# general_Interface.net
KiCad netlist of a schematic drawn in Altium Designer
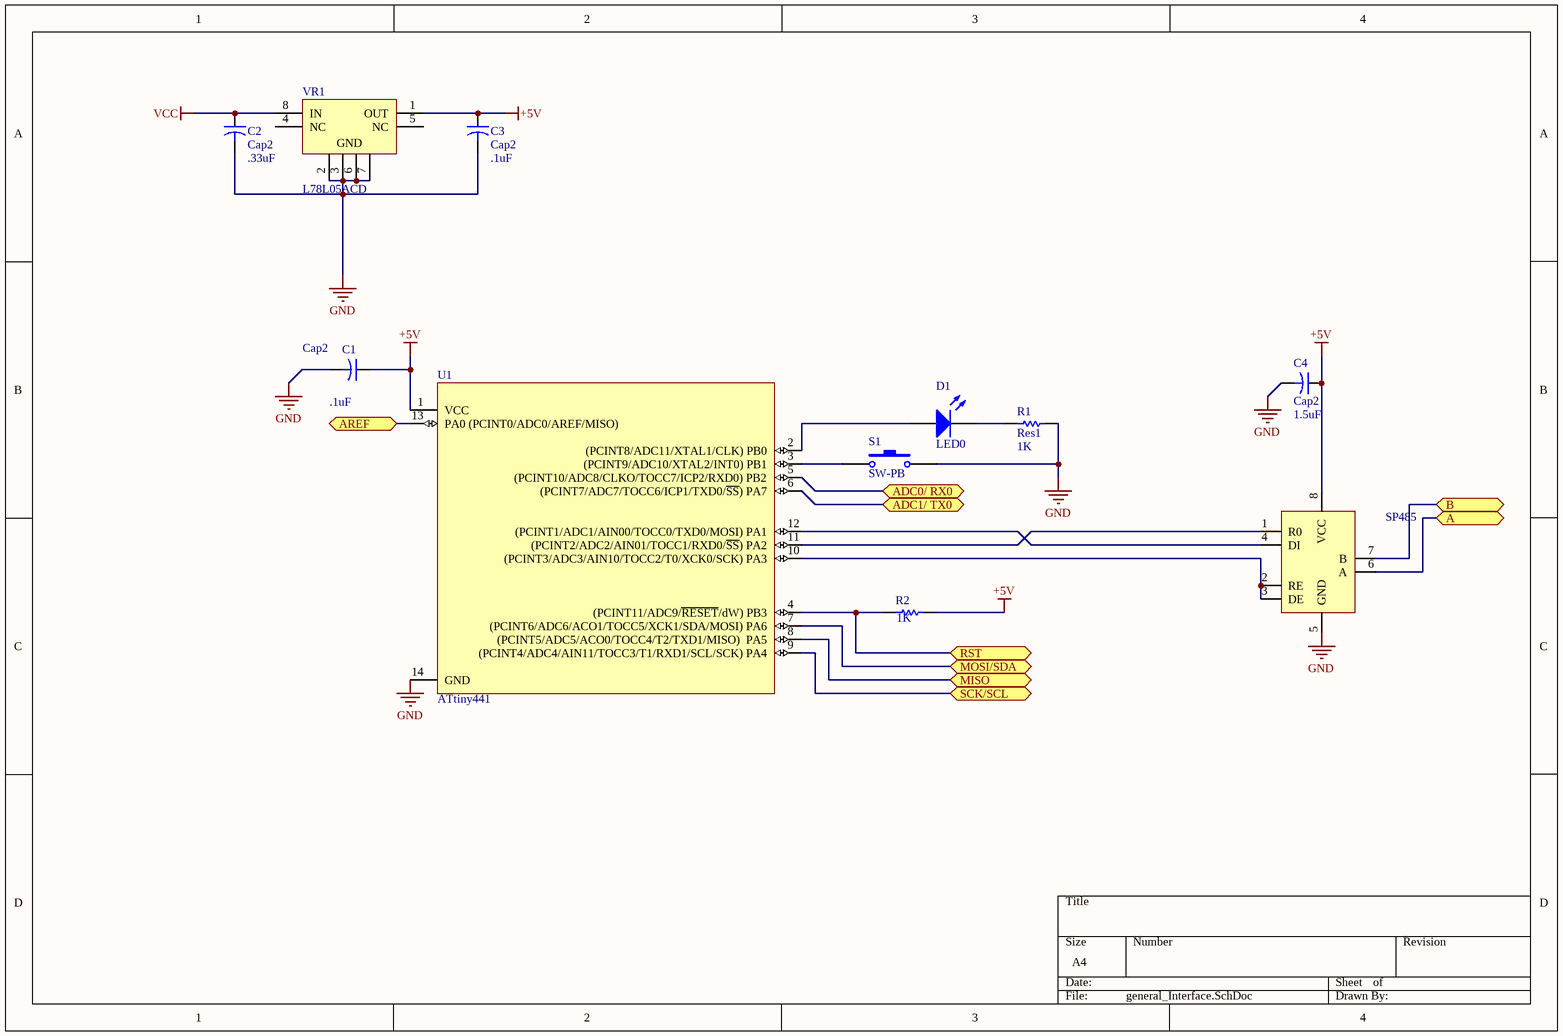
[diagram p0: general_Interface.SchDoc]

(export (version "E")
  (design (tool "Eeschema 10.0.6"))
  (components
    (comp (ref "C1")
      (value "Cap2")
      (footprint "6-0805_N")
      (description "Capacitor")
      (fields (field (name "ALTIUM_VALUE") ".1uF") (field (name "PUBLISHER") "Altium Limited"))
      (libsource (lib "Miscellaneous Devices") (part "Cap2"))
    )
    (comp (ref "C2")
      (value "Cap2")
      (footprint "6-0805_N")
      (description "Capacitor")
      (fields (field (name "ALTIUM_VALUE") ".33uF") (field (name "PUBLISHER") "Altium Limited"))
      (libsource (lib "Miscellaneous Devices") (part "Cap2"))
    )
    (comp (ref "C3")
      (value "Cap2")
      (footprint "6-0805_N")
      (description "Capacitor")
      (fields (field (name "ALTIUM_VALUE") ".1uF") (field (name "PUBLISHER") "Altium Limited"))
      (libsource (lib "Miscellaneous Devices") (part "Cap2"))
    )
    (comp (ref "C4")
      (value "Cap2")
      (footprint "6-0805_N")
      (description "Capacitor")
      (fields (field (name "ALTIUM_VALUE") "1.5uF") (field (name "PUBLISHER") "Altium Limited"))
      (libsource (lib "Miscellaneous Devices") (part "Cap2"))
    )
    (comp (ref "D1")
      (value "LED0")
      (footprint "1608[0603]")
      (description "Typical INFRARED GaAs LED")
      (fields (field (name "PUBLISHER") "Altium Limited"))
      (libsource (lib "Miscellaneous Devices") (part "LED0"))
    )
    (comp (ref "R1")
      (value "Res1")
      (footprint "6-0805_N")
      (description "Resistor")
      (fields (field (name "ALTIUM_VALUE") "1K") (field (name "PUBLISHER") "Altium Limited"))
      (libsource (lib "Miscellaneous Devices") (part "Res1"))
    )
    (comp (ref "R2")
      (value "1K")
      (footprint "6-0805_N")
      (description "Resistor")
      (fields (field (name "Comment") "Res1") (field (name "PUBLISHER") "Altium Limited"))
      (libsource (lib "Miscellaneous Devices") (part "Res1"))
    )
    (comp (ref "S1")
      (value "SW-PB")
      (footprint "ADTSM3")
      (description "Switch")
      (fields (field (name "PUBLISHER") "Altium Limited"))
      (libsource (lib "Miscellaneous Devices") (part "SW-PB"))
    )
    (comp (ref "SP485") (value "SP485") (footprint "8S1_M") (libsource (lib "MABSS") (part "SP485")))
    (comp (ref "U1") (value "ATtiny441") (footprint "6ST1_L") (libsource (lib "MABSS") (part "ATtiny441")))
    (comp (ref "VR1")
      (value "L78L05ACD")
      (footprint "SO8_N")
      (description "Positive Voltage Regulator")
      (fields (field (name "PUBLISHER") "Altium Limited"))
      (libsource (lib "ST Power Mgt Voltage Regulator") (part "L78L05ACD"))
    )
  )
  (nets
    (net (code "1") (name "+5V") (class "Default")
      (node (ref "C1") (pin "1") (pinfunction "1_1") (pintype "passive"))
      (node (ref "C3") (pin "1") (pinfunction "1_1") (pintype "passive"))
      (node (ref "C4") (pin "1") (pinfunction "1_1") (pintype "passive"))
      (node (ref "R2") (pin "2") (pinfunction "2_2") (pintype "passive"))
      (node (ref "SP485") (pin "8") (pinfunction "VCC_8") (pintype "passive"))
      (node (ref "U1") (pin "1") (pinfunction "VCC_1") (pintype "power_in"))
      (node (ref "VR1") (pin "1") (pinfunction "OUT_1") (pintype "power_in"))
    )
    (net (code "2") (name "/A") (class "Default")
      (node (ref "SP485") (pin "6") (pinfunction "A_6") (pintype "passive"))
    )
    (net (code "3") (name "/ADC0{slash} RX0") (class "Default")
      (node (ref "U1") (pin "5") (pinfunction "(PCINT10/ADC8/CLKO/TOCC7/ICP2/RXD0)_PB2_5") (pintype "bidirectional"))
    )
    (net (code "4") (name "/ADC1{slash} TX0") (class "Default")
      (node (ref "U1") (pin "6") (pinfunction "(PCINT7/ADC7/TOCC6/ICP1/TXD0/~{SS})_PA7_6") (pintype "bidirectional"))
    )
    (net (code "5") (name "/AREF") (class "Default")
      (node (ref "U1") (pin "13") (pinfunction "PA0_(PCINT0/ADC0/AREF/MISO)_13") (pintype "bidirectional"))
    )
    (net (code "6") (name "/B") (class "Default")
      (node (ref "SP485") (pin "7") (pinfunction "B_7") (pintype "passive"))
    )
    (net (code "7") (name "/MISO") (class "Default")
      (node (ref "U1") (pin "8") (pinfunction "(PCINT5/ADC5/ACO0/TOCC4/T2/TXD1/MISO)__PA5_8") (pintype "bidirectional"))
    )
    (net (code "8") (name "/MOSI{slash}SDA") (class "Default")
      (node (ref "U1") (pin "7") (pinfunction "(PCINT6/ADC6/ACO1/TOCC5/XCK1/SDA/MOSI)_PA6_7") (pintype "bidirectional"))
    )
    (net (code "9") (name "/RST") (class "Default")
      (node (ref "R2") (pin "1") (pinfunction "1_1") (pintype "passive"))
      (node (ref "U1") (pin "4") (pinfunction "(PCINT11/ADC9/~{RESET}/dW)_PB3_4") (pintype "bidirectional"))
    )
    (net (code "10") (name "/SCK{slash}SCL") (class "Default")
      (node (ref "U1") (pin "9") (pinfunction "(PCINT4/ADC4/AIN11/TOCC3/T1/RXD1/SCL/SCK)_PA4_9") (pintype "bidirectional"))
    )
    (net (code "11") (name "GND") (class "Default")
      (node (ref "C1") (pin "2") (pinfunction "2_2") (pintype "passive"))
      (node (ref "C2") (pin "2") (pinfunction "2_2") (pintype "passive"))
      (node (ref "C3") (pin "2") (pinfunction "2_2") (pintype "passive"))
      (node (ref "C4") (pin "2") (pinfunction "2_2") (pintype "passive"))
      (node (ref "R1") (pin "2") (pinfunction "2_2") (pintype "passive"))
      (node (ref "S1") (pin "2") (pinfunction "2_2") (pintype "passive"))
      (node (ref "SP485") (pin "5") (pinfunction "GND_5") (pintype "passive"))
      (node (ref "U1") (pin "14") (pinfunction "GND_14") (pintype "power_in"))
      (node (ref "VR1") (pin "2") (pinfunction "GND_2") (pintype "power_in"))
      (node (ref "VR1") (pin "3") (pinfunction "GND_3") (pintype "power_in"))
      (node (ref "VR1") (pin "6") (pinfunction "GND_6") (pintype "power_in"))
      (node (ref "VR1") (pin "7") (pinfunction "GND_7") (pintype "power_in"))
    )
    (net (code "12") (name "Net-(D1-A)") (class "Default")
      (node (ref "D1") (pin "1") (pinfunction "A_1") (pintype "passive"))
      (node (ref "U1") (pin "2") (pinfunction "(PCINT8/ADC11/XTAL1/CLK)_PB0_2") (pintype "bidirectional"))
    )
    (net (code "13") (name "Net-(D1-K)") (class "Default")
      (node (ref "D1") (pin "2") (pinfunction "K_2") (pintype "passive"))
      (node (ref "R1") (pin "1") (pinfunction "1_1") (pintype "passive"))
    )
    (net (code "14") (name "Net-(SP485-DE)") (class "Default")
      (node (ref "SP485") (pin "2") (pinfunction "RE_2") (pintype "passive"))
      (node (ref "SP485") (pin "3") (pinfunction "DE_3") (pintype "passive"))
      (node (ref "U1") (pin "10") (pinfunction "(PCINT3/ADC3/AIN10/TOCC2/T0/XCK0/SCK)_PA3_10") (pintype "bidirectional"))
    )
    (net (code "15") (name "Net-(SP485-DI)") (class "Default")
      (node (ref "SP485") (pin "4") (pinfunction "DI_4") (pintype "passive"))
      (node (ref "U1") (pin "12") (pinfunction "(PCINT1/ADC1/AIN00/TOCC0/TXD0/MOSI)_PA1_12") (pintype "bidirectional"))
    )
    (net (code "16") (name "Net-(SP485-R0)") (class "Default")
      (node (ref "SP485") (pin "1") (pinfunction "R0_1") (pintype "passive"))
      (node (ref "U1") (pin "11") (pinfunction "(PCINT2/ADC2/AIN01/TOCC1/RXD0/~{SS})_PA2_11") (pintype "bidirectional"))
    )
    (net (code "17") (name "Net-(U1-(PCINT9{slash}ADC10{slash}XTAL2{slash}INT0)_PB1)") (class "Default")
      (node (ref "S1") (pin "1") (pinfunction "1_1") (pintype "passive"))
      (node (ref "U1") (pin "3") (pinfunction "(PCINT9/ADC10/XTAL2/INT0)_PB1_3") (pintype "bidirectional"))
    )
    (net (code "18") (name "VCC") (class "Default")
      (node (ref "C2") (pin "1") (pinfunction "1_1") (pintype "passive"))
      (node (ref "VR1") (pin "8") (pinfunction "IN_8") (pintype "power_in"))
    )
    (net (code "19") (name "unconnected-(VR1-NC-Pad4)") (class "Default")
      (node (ref "VR1") (pin "4") (pinfunction "NC_4") (pintype "passive"))
    )
    (net (code "20") (name "unconnected-(VR1-NC-Pad5)") (class "Default")
      (node (ref "VR1") (pin "5") (pinfunction "NC_5") (pintype "passive"))
    )
  )
)
